# Bluetooth_Module_V1.net
KiCad netlist of a schematic drawn in Altium Designer
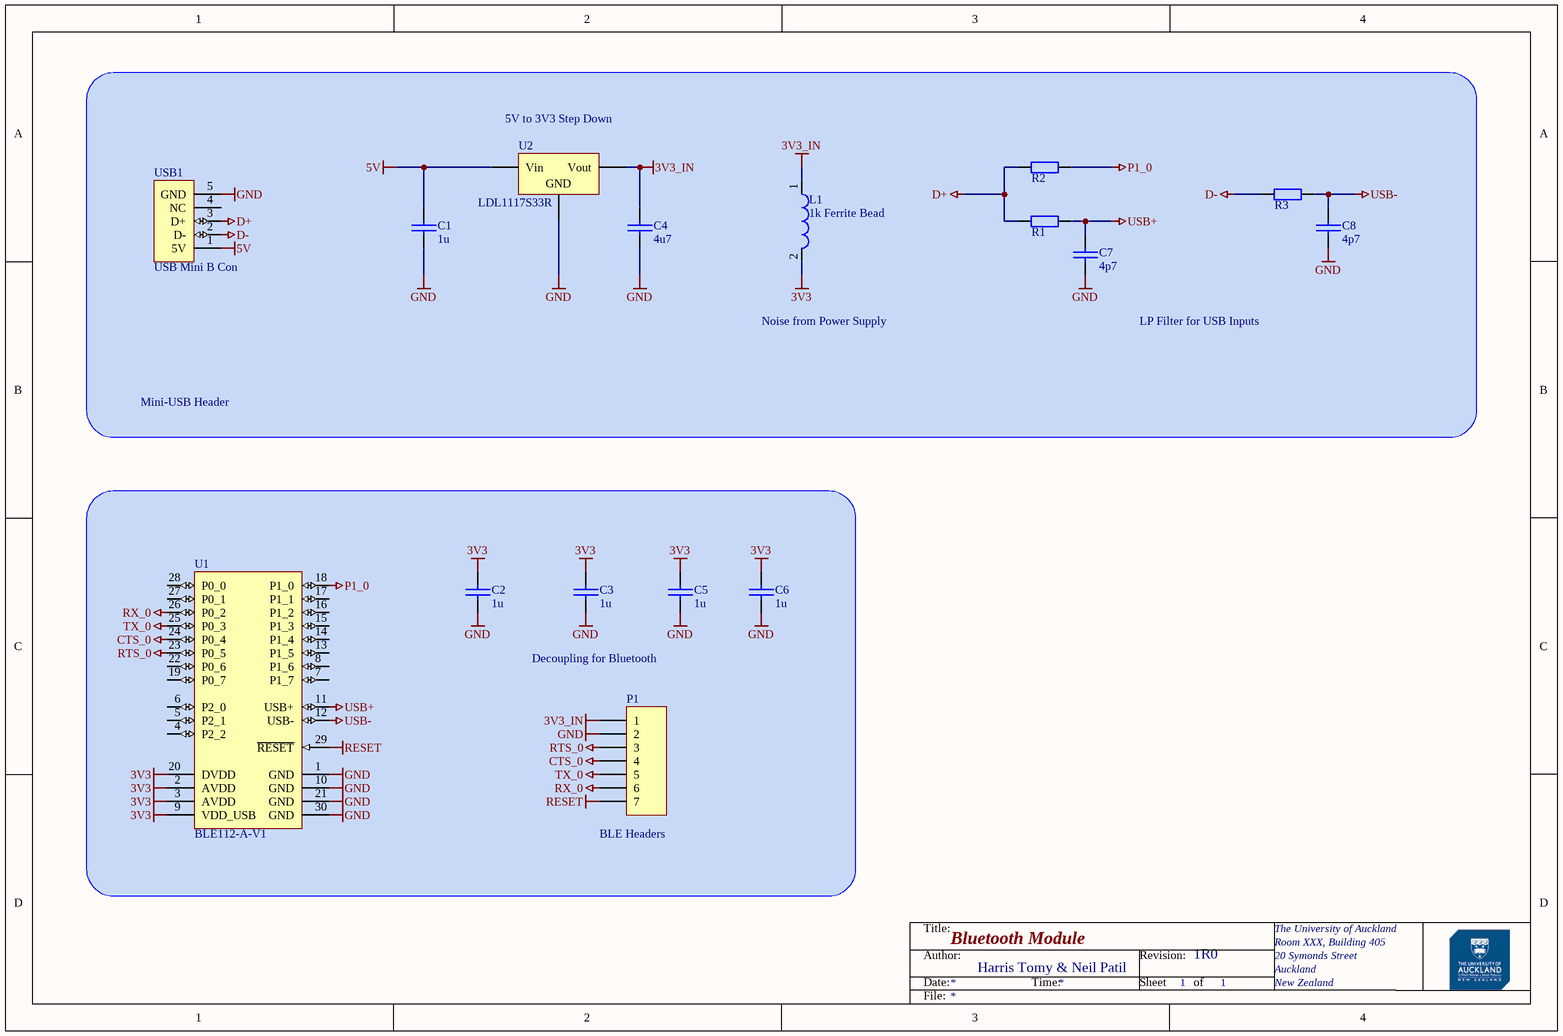
[diagram p0: Bluetooth_Module_V1.SchDoc]

(export (version "E")
  (design (tool "Eeschema 10.0.6"))
  (components
    (comp (ref "C1")
      (value "1u")
      (footprint "C0805")
      (description "CCAP0805")
      (fields (field (name "MPN") "?"))
      (libsource (lib "E209_Lib") (part "CCAP0805"))
    )
    (comp (ref "C2")
      (value "1u")
      (footprint "C0805")
      (description "CCAP0805")
      (fields (field (name "MPN") "?"))
      (libsource (lib "E209_Lib") (part "CCAP0805"))
    )
    (comp (ref "C3")
      (value "1u")
      (footprint "C0805")
      (description "CCAP0805")
      (fields (field (name "MPN") "?"))
      (libsource (lib "E209_Lib") (part "CCAP0805"))
    )
    (comp (ref "C4")
      (value "4u7")
      (footprint "C1206")
      (description "CAP CER 0.1UF 100V C0G 1206")
      (fields (field (name "MPN") "C3216C0G2A104J160AC") (field (name "MANUFACTURER") "TDK Corporation"))
      (libsource (lib "E209_Lib") (part "Cap CER Decoup C3216C0G2A104J160AC"))
    )
    (comp (ref "C5")
      (value "1u")
      (footprint "C0805")
      (description "CCAP0805")
      (fields (field (name "MPN") "?"))
      (libsource (lib "E209_Lib") (part "CCAP0805"))
    )
    (comp (ref "C6")
      (value "1u")
      (footprint "C0805")
      (description "CCAP0805")
      (fields (field (name "MPN") "?"))
      (libsource (lib "E209_Lib") (part "CCAP0805"))
    )
    (comp (ref "C7")
      (value "4p7")
      (footprint "C0805")
      (description "CCAP0805")
      (fields (field (name "MPN") "?"))
      (libsource (lib "E209_Lib") (part "CCAP0805"))
    )
    (comp (ref "C8")
      (value "4p7")
      (footprint "C0805")
      (description "CCAP0805")
      (fields (field (name "MPN") "?"))
      (libsource (lib "E209_Lib") (part "CCAP0805"))
    )
    (comp (ref "L1")
      (value "1k Ferrite Bead")
      (footprint "SMD-1206")
      (description "SMD EMI Suppression Ferrite Bead WE-CBF, Z = 120 Ohm")
      (fields (field (name "PARTNUMBER") "742792113"))
      (libsource (lib "FE_Bead_1206") (part "742792113"))
    )
    (comp (ref "P1")
      (value "BLE Headers")
      (footprint "HDR1X7")
      (description "Header, 7-Pin")
      (fields (field (name "PUBLISHER") "Altium Limited"))
      (libsource (lib "Miscellaneous Connectors") (part "Header 7"))
    )
    (comp (ref "R1")
      (value "Resistor 0805")
      (footprint "R0805")
      (description "RES0805")
      (fields (field (name "MPN") "?"))
      (libsource (lib "E209_Lib") (part "RES0805"))
    )
    (comp (ref "R2")
      (value "Resistor 0805")
      (footprint "R0805")
      (description "RES0805")
      (fields (field (name "MPN") "?"))
      (libsource (lib "") (part "RES0805_1"))
    )
    (comp (ref "R3")
      (value "Resistor 0805")
      (footprint "R0805")
      (description "RES0805")
      (fields (field (name "MPN") "?"))
      (libsource (lib "E209_Lib") (part "RES0805"))
    )
    (comp (ref "U1")
      (value "BLE112-A-V1")
      (footprint "BLUE-BLE112-A-V1_V")
      (libsource (lib "BLE112") (part "BLE112-A-V1"))
    )
    (comp (ref "U2")
      (value "LDL1117S33R")
      (footprint "SOT223L")
      (description "IC REG LINEAR 3.3V 1.2A SOT223")
      (fields (field (name "MANUFACTURER") "STMicroelectronics"))
      (libsource (lib "E209_Lib") (part "LDO LDL1117S33R"))
    )
    (comp (ref "USB1")
      (value "USB Mini B Con")
      (footprint "USB_UJ2MAB")
      (libsource (lib "CommonDevices_V1") (part "USBMiniB"))
    )
  )
  (nets
    (net (code "1") (name "3V3") (class "Default")
      (node (ref "C2") (pin "2") (pinfunction "2_2") (pintype "passive"))
      (node (ref "C3") (pin "2") (pinfunction "2_2") (pintype "passive"))
      (node (ref "C5") (pin "2") (pinfunction "2_2") (pintype "passive"))
      (node (ref "C6") (pin "2") (pinfunction "2_2") (pintype "passive"))
      (node (ref "L1") (pin "2") (pinfunction "2_2") (pintype "passive"))
      (node (ref "U1") (pin "2") (pinfunction "AVDD_2") (pintype "power_in"))
      (node (ref "U1") (pin "20") (pinfunction "DVDD_20") (pintype "power_in"))
      (node (ref "U1") (pin "3") (pinfunction "AVDD_3") (pintype "power_in"))
      (node (ref "U1") (pin "9") (pinfunction "VDD_USB_9") (pintype "power_in"))
    )
    (net (code "2") (name "3V3_IN") (class "Default")
      (node (ref "C4") (pin "2") (pinfunction "2_2") (pintype "passive"))
      (node (ref "L1") (pin "1") (pinfunction "1_1") (pintype "passive"))
      (node (ref "P1") (pin "1") (pinfunction "1_1") (pintype "passive"))
      (node (ref "U2") (pin "2") (pinfunction "Vout_2") (pintype "passive"))
    )
    (net (code "3") (name "5V") (class "Default")
      (node (ref "C1") (pin "2") (pinfunction "2_2") (pintype "passive"))
      (node (ref "U2") (pin "3") (pinfunction "Vin_3") (pintype "passive"))
      (node (ref "USB1") (pin "1") (pinfunction "5V_1") (pintype "passive"))
    )
    (net (code "4") (name "CTS_0") (class "Default")
      (node (ref "P1") (pin "4") (pinfunction "4_4") (pintype "passive"))
      (node (ref "U1") (pin "24") (pinfunction "P0_4_24") (pintype "bidirectional"))
    )
    (net (code "5") (name "D+") (class "Default")
      (node (ref "R1") (pin "2") (pinfunction "2_2") (pintype "passive"))
      (node (ref "R2") (pin "1") (pinfunction "1_1") (pintype "passive"))
      (node (ref "USB1") (pin "3") (pinfunction "D+_3") (pintype "bidirectional"))
    )
    (net (code "6") (name "D-") (class "Default")
      (node (ref "R3") (pin "2") (pinfunction "2_2") (pintype "passive"))
      (node (ref "USB1") (pin "2") (pinfunction "D-_2") (pintype "bidirectional"))
    )
    (net (code "7") (name "GND") (class "Default")
      (node (ref "C1") (pin "1") (pinfunction "1_1") (pintype "passive"))
      (node (ref "C2") (pin "1") (pinfunction "1_1") (pintype "passive"))
      (node (ref "C3") (pin "1") (pinfunction "1_1") (pintype "passive"))
      (node (ref "C4") (pin "1") (pinfunction "1_1") (pintype "passive"))
      (node (ref "C5") (pin "1") (pinfunction "1_1") (pintype "passive"))
      (node (ref "C6") (pin "1") (pinfunction "1_1") (pintype "passive"))
      (node (ref "C7") (pin "1") (pinfunction "1_1") (pintype "passive"))
      (node (ref "C8") (pin "1") (pinfunction "1_1") (pintype "passive"))
      (node (ref "P1") (pin "2") (pinfunction "2_2") (pintype "passive"))
      (node (ref "U1") (pin "1") (pinfunction "GND_1") (pintype "power_in"))
      (node (ref "U1") (pin "10") (pinfunction "GND_10") (pintype "power_in"))
      (node (ref "U1") (pin "21") (pinfunction "GND_21") (pintype "power_in"))
      (node (ref "U1") (pin "30") (pinfunction "GND_30") (pintype "power_in"))
      (node (ref "U2") (pin "1") (pinfunction "GND_1") (pintype "passive"))
      (node (ref "USB1") (pin "5") (pinfunction "GND_5") (pintype "passive"))
    )
    (net (code "8") (name "P1_0") (class "Default")
      (node (ref "R2") (pin "2") (pinfunction "2_2") (pintype "passive"))
      (node (ref "U1") (pin "18") (pinfunction "P1_0_18") (pintype "bidirectional"))
    )
    (net (code "9") (name "RESET") (class "Default")
      (node (ref "P1") (pin "7") (pinfunction "7_7") (pintype "passive"))
      (node (ref "U1") (pin "29") (pinfunction "~{RESET}_29") (pintype "input"))
    )
    (net (code "10") (name "RTS_0") (class "Default")
      (node (ref "P1") (pin "3") (pinfunction "3_3") (pintype "passive"))
      (node (ref "U1") (pin "23") (pinfunction "P0_5_23") (pintype "bidirectional"))
    )
    (net (code "11") (name "RX_0") (class "Default")
      (node (ref "P1") (pin "6") (pinfunction "6_6") (pintype "passive"))
      (node (ref "U1") (pin "26") (pinfunction "P0_2_26") (pintype "bidirectional"))
    )
    (net (code "12") (name "TX_0") (class "Default")
      (node (ref "P1") (pin "5") (pinfunction "5_5") (pintype "passive"))
      (node (ref "U1") (pin "25") (pinfunction "P0_3_25") (pintype "bidirectional"))
    )
    (net (code "13") (name "USB+") (class "Default")
      (node (ref "C7") (pin "2") (pinfunction "2_2") (pintype "passive"))
      (node (ref "R1") (pin "1") (pinfunction "1_1") (pintype "passive"))
      (node (ref "U1") (pin "11") (pinfunction "USB+_11") (pintype "bidirectional"))
    )
    (net (code "14") (name "USB-") (class "Default")
      (node (ref "C8") (pin "2") (pinfunction "2_2") (pintype "passive"))
      (node (ref "R3") (pin "1") (pinfunction "1_1") (pintype "passive"))
      (node (ref "U1") (pin "12") (pinfunction "USB-_12") (pintype "bidirectional"))
    )
    (net (code "15") (name "unconnected-(U1-P0_0-Pad28)") (class "Default")
      (node (ref "U1") (pin "28") (pinfunction "P0_0_28") (pintype "bidirectional"))
    )
    (net (code "16") (name "unconnected-(U1-P0_1-Pad27)") (class "Default")
      (node (ref "U1") (pin "27") (pinfunction "P0_1_27") (pintype "bidirectional"))
    )
    (net (code "17") (name "unconnected-(U1-P0_6-Pad22)") (class "Default")
      (node (ref "U1") (pin "22") (pinfunction "P0_6_22") (pintype "bidirectional"))
    )
    (net (code "18") (name "unconnected-(U1-P0_7-Pad19)") (class "Default")
      (node (ref "U1") (pin "19") (pinfunction "P0_7_19") (pintype "bidirectional"))
    )
    (net (code "19") (name "unconnected-(U1-P1_1-Pad17)") (class "Default")
      (node (ref "U1") (pin "17") (pinfunction "P1_1_17") (pintype "bidirectional"))
    )
    (net (code "20") (name "unconnected-(U1-P1_2-Pad16)") (class "Default")
      (node (ref "U1") (pin "16") (pinfunction "P1_2_16") (pintype "bidirectional"))
    )
    (net (code "21") (name "unconnected-(U1-P1_3-Pad15)") (class "Default")
      (node (ref "U1") (pin "15") (pinfunction "P1_3_15") (pintype "bidirectional"))
    )
    (net (code "22") (name "unconnected-(U1-P1_4-Pad14)") (class "Default")
      (node (ref "U1") (pin "14") (pinfunction "P1_4_14") (pintype "bidirectional"))
    )
    (net (code "23") (name "unconnected-(U1-P1_5-Pad13)") (class "Default")
      (node (ref "U1") (pin "13") (pinfunction "P1_5_13") (pintype "bidirectional"))
    )
    (net (code "24") (name "unconnected-(U1-P1_6-Pad8)") (class "Default")
      (node (ref "U1") (pin "8") (pinfunction "P1_6_8") (pintype "bidirectional"))
    )
    (net (code "25") (name "unconnected-(U1-P1_7-Pad7)") (class "Default")
      (node (ref "U1") (pin "7") (pinfunction "P1_7_7") (pintype "bidirectional"))
    )
    (net (code "26") (name "unconnected-(U1-P2_0-Pad6)") (class "Default")
      (node (ref "U1") (pin "6") (pinfunction "P2_0_6") (pintype "bidirectional"))
    )
    (net (code "27") (name "unconnected-(U1-P2_1-Pad5)") (class "Default")
      (node (ref "U1") (pin "5") (pinfunction "P2_1_5") (pintype "bidirectional"))
    )
    (net (code "28") (name "unconnected-(U1-P2_2-Pad4)") (class "Default")
      (node (ref "U1") (pin "4") (pinfunction "P2_2_4") (pintype "bidirectional"))
    )
    (net (code "29") (name "unconnected-(USB1-NC-Pad4)") (class "Default")
      (node (ref "USB1") (pin "4") (pinfunction "NC_4") (pintype "passive"))
    )
  )
)
